# Peripherals.net
KiCad netlist of a schematic drawn in Altium Designer
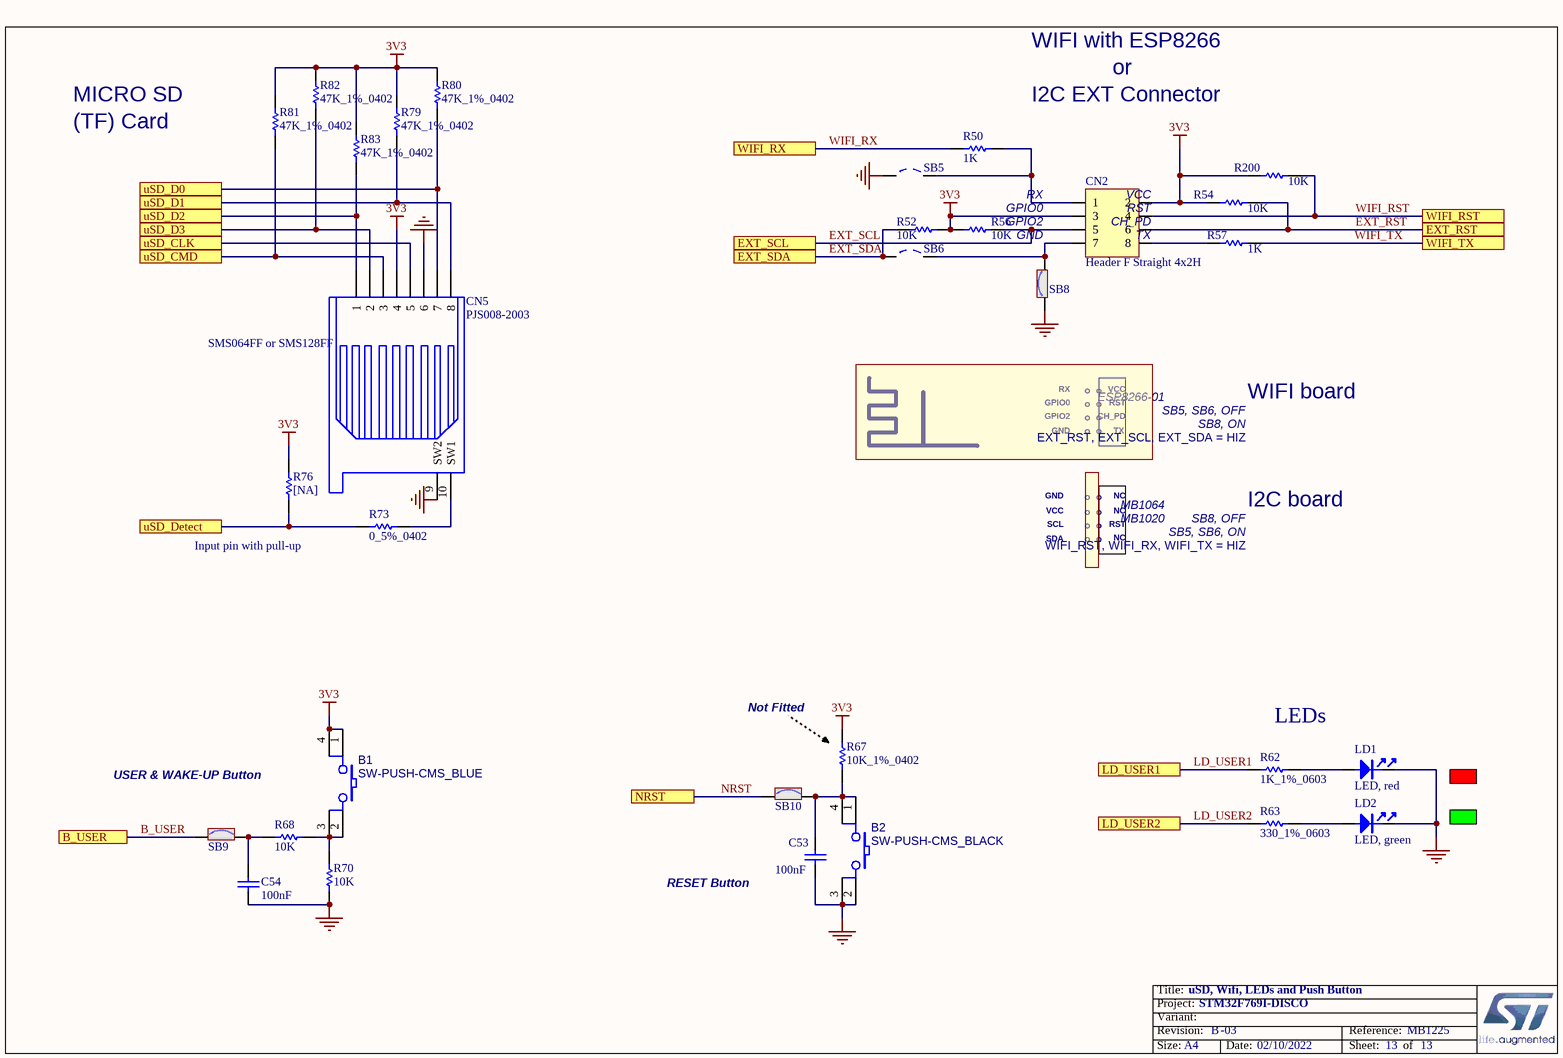
[diagram p0: Peripherals.SchDoc]

(export (version "E")
  (design (tool "Eeschema 10.0.6"))
  (components
    (comp (ref "B1")
      (value "SW-PUSH-CMS_BLUE")
      (footprint "PB10")
      (description "Non-Open Push-Button 0.1A 24V")
      (fields (field (name "PROVIDED") "Sub Co"))
      (libsource (lib "MCD_TOOLS_MISCELLANEOUS") (part "SW-PUSH-CMS_BLUE"))
    )
    (comp (ref "B2")
      (value "SW-PUSH-CMS_BLACK")
      (footprint "PB10")
      (description "Non-Open Push-Button 0.1A 24V")
      (fields (field (name "PROVIDED") "Sub Co"))
      (libsource (lib "MCD_TOOLS_MISCELLANEOUS") (part "SW-PUSH-CMS_BLACK"))
    )
    (comp (ref "C53")
      (value "100nF")
      (footprint "0402C")
      (description "Capacitor,100nF,16V,X7R,10%,0402,YAGEO")
      (libsource (lib "MCD_TOOLS") (part "Cap_100nF_X7R_10%_0402"))
    )
    (comp (ref "C54")
      (value "100nF")
      (footprint "0402C")
      (description "Capacitor,100nF,16V,X7R,10%,0402,YAGEO")
      (libsource (lib "MCD_TOOLS") (part "Cap_100nF_X7R_10%_0402"))
    )
    (comp (ref "CN2")
      (value "Header F Straight 4x2H")
      (footprint "HDR_2X4_2R54")
      (description "Header Female, 4-Pin, Dual row, Straight")
      (libsource (lib "MCD_TOOLS_CONNECTOR") (part "Header 4X2F"))
    )
    (comp (ref "CN5")
      (value "PJS008-2003")
      (footprint "MSD_PJS008_")
      (description "Memory Card Connectors MicroSD Card Conn Revrs Mnt Push-Push")
      (libsource (lib "MCD_TOOLS_CONNECTOR") (part "microSD-PJS008-2003"))
    )
    (comp (ref "LD1")
      (value "LED, red")
      (footprint "0603D")
      (description "LED, red, 0603")
      (libsource (lib "MCD_TOOLS_MISCELLANEOUS") (part "LED_red"))
    )
    (comp (ref "LD2")
      (value "LED, green")
      (footprint "0603D")
      (description "LED, green, 0603")
      (libsource (lib "MCD_TOOLS_MISCELLANEOUS") (part "LED_green"))
    )
    (comp (ref "R50")
      (value "1K")
      (footprint "0402R")
      (description "Resistor,1K,0402,1%,YAGEO")
      (libsource (lib "MCD_TOOLS_RESISTOR") (part "Res_1K_1%_0402"))
    )
    (comp (ref "R52")
      (value "10K")
      (footprint "0402R")
      (description "Resistor,10K,0402,1%,YAGEO")
      (libsource (lib "MCD_TOOLS") (part "Res_10K_1%_0402"))
    )
    (comp (ref "R54")
      (value "10K")
      (footprint "0402R")
      (description "Resistor,10K,0402,1%,YAGEO")
      (libsource (lib "MCD_TOOLS") (part "Res_10K_1%_0402"))
    )
    (comp (ref "R56")
      (value "10K")
      (footprint "0402R")
      (description "Resistor,10K,0402,1%,YAGEO")
      (libsource (lib "MCD_TOOLS") (part "Res_10K_1%_0402"))
    )
    (comp (ref "R57")
      (value "1K")
      (footprint "0402R")
      (description "Resistor,1K,0402,1%,YAGEO")
      (libsource (lib "MCD_TOOLS_RESISTOR") (part "Res_1K_1%_0402"))
    )
    (comp (ref "R62")
      (value "1K_1%_0603")
      (footprint "0603R")
      (description "Resistor,1K,0603,1%,YAGEO")
      (libsource (lib "MCD_TOOLS_RESISTOR") (part "Res_1K_1%_0603"))
    )
    (comp (ref "R63")
      (value "330_1%_0603")
      (footprint "0603R")
      (description "Resistor,330,0603,1%,YAGEO")
      (libsource (lib "MCD_TOOLS_RESISTOR") (part "Res_330_1%_0603"))
    )
    (comp (ref "R67")
      (value "10K_1%_0402")
      (footprint "0402R")
      (description "Resistor,10K,0402,1%,YAGEO")
      (libsource (lib "MCD_TOOLS") (part "Res_10K_1%_0402"))
    )
    (comp (ref "R68")
      (value "10K")
      (footprint "0402R")
      (description "Resistor,10K,0402,1%,YAGEO")
      (libsource (lib "MCD_TOOLS") (part "Res_10K_1%_0402"))
    )
    (comp (ref "R70")
      (value "10K")
      (footprint "0402R")
      (description "Resistor,10K,0402,1%,YAGEO")
      (libsource (lib "MCD_TOOLS") (part "Res_10K_1%_0402"))
    )
    (comp (ref "R73")
      (value "0_5%_0402")
      (footprint "0402R")
      (description "Resistor,0,0402,5%,YAGEO")
      (libsource (lib "MCD_TOOLS") (part "Res_0_5%_0402"))
    )
    (comp (ref "R76")
      (value "[NA]")
      (footprint "0402R")
      (description "Resistor,[NA],0402")
      (libsource (lib "MCD_TOOLS") (part "Res_NA_0402"))
    )
    (comp (ref "R79")
      (value "47K_1%_0402")
      (footprint "0402R")
      (description "Resistor,47K,0402,1%,YAGEO")
      (libsource (lib "MCD_TOOLS") (part "Res_47K_1%_0402"))
    )
    (comp (ref "R80")
      (value "47K_1%_0402")
      (footprint "0402R")
      (description "Resistor,47K,0402,1%,YAGEO")
      (libsource (lib "MCD_TOOLS") (part "Res_47K_1%_0402"))
    )
    (comp (ref "R81")
      (value "47K_1%_0402")
      (footprint "0402R")
      (description "Resistor,47K,0402,1%,YAGEO")
      (libsource (lib "MCD_TOOLS") (part "Res_47K_1%_0402"))
    )
    (comp (ref "R82")
      (value "47K_1%_0402")
      (footprint "0402R")
      (description "Resistor,47K,0402,1%,YAGEO")
      (libsource (lib "MCD_TOOLS") (part "Res_47K_1%_0402"))
    )
    (comp (ref "R83")
      (value "47K_1%_0402")
      (footprint "0402R")
      (description "Resistor,47K,0402,1%,YAGEO")
      (libsource (lib "MCD_TOOLS") (part "Res_47K_1%_0402"))
    )
    (comp (ref "R200")
      (value "10K")
      (footprint "0402R")
      (description "Resistor,10K,0402,1%,YAGEO")
      (libsource (lib "MCD_TOOLS") (part "Res_10K_1%_0402"))
    )
    (comp (ref "SB5")
      (value "Solder Bridge OFF")
      (footprint "JP2_SMD")
      (libsource (lib "MCD_TOOLS") (part "SB_OFF"))
    )
    (comp (ref "SB6")
      (value "Solder Bridge OFF")
      (footprint "JP2_SMD")
      (libsource (lib "MCD_TOOLS") (part "SB_OFF"))
    )
    (comp (ref "SB8") (value "Solder Bridge ON") (footprint "JP2_SMD") (libsource (lib "") (part "SB_ON_1")))
    (comp (ref "SB9")
      (value "Solder Bridge ON")
      (footprint "JP2_SMD")
      (libsource (lib "MCD_TOOLS") (part "SB_ON"))
    )
    (comp (ref "SB10")
      (value "Solder Bridge ON")
      (footprint "JP2_SMD")
      (libsource (lib "MCD_TOOLS") (part "SB_ON"))
    )
  )
  (nets
    (net (code "1") (name "/B_USER") (class "Default")
      (node (ref "SB9") (pin "1") (pinfunction "1_1") (pintype "passive"))
    )
    (net (code "2") (name "/EXT_RST") (class "Default")
      (node (ref "CN2") (pin "6") (pinfunction "6_6") (pintype "passive"))
      (node (ref "R54") (pin "2") (pinfunction "2_2") (pintype "passive"))
    )
    (net (code "3") (name "/EXT_SCL") (class "Default")
      (node (ref "CN2") (pin "5") (pinfunction "5_5") (pintype "passive"))
      (node (ref "R56") (pin "2") (pinfunction "2_2") (pintype "passive"))
    )
    (net (code "4") (name "/EXT_SDA") (class "Default")
      (node (ref "R52") (pin "1") (pinfunction "1_1") (pintype "passive"))
      (node (ref "SB6") (pin "1") (pinfunction "1_1") (pintype "passive"))
    )
    (net (code "5") (name "/LD_USER1") (class "Default")
      (node (ref "R62") (pin "1") (pinfunction "1_1") (pintype "passive"))
    )
    (net (code "6") (name "/LD_USER2") (class "Default")
      (node (ref "R63") (pin "1") (pinfunction "1_1") (pintype "passive"))
    )
    (net (code "7") (name "/NRST") (class "Default")
      (node (ref "SB10") (pin "1") (pinfunction "1_1") (pintype "passive"))
    )
    (net (code "8") (name "/WIFI_RST") (class "Default")
      (node (ref "CN2") (pin "4") (pinfunction "4_4") (pintype "passive"))
      (node (ref "R200") (pin "2") (pinfunction "2_2") (pintype "passive"))
    )
    (net (code "9") (name "/WIFI_RX") (class "Default")
      (node (ref "R50") (pin "1") (pinfunction "1_1") (pintype "passive"))
    )
    (net (code "10") (name "/WIFI_TX") (class "Default")
      (node (ref "R57") (pin "2") (pinfunction "2_2") (pintype "passive"))
    )
    (net (code "11") (name "/uSD_CLK") (class "Default")
      (node (ref "CN5") (pin "5") (pinfunction "5_5") (pintype "passive"))
    )
    (net (code "12") (name "/uSD_CMD") (class "Default")
      (node (ref "CN5") (pin "3") (pinfunction "3_3") (pintype "passive"))
      (node (ref "R81") (pin "1") (pinfunction "1_1") (pintype "passive"))
    )
    (net (code "13") (name "/uSD_D0") (class "Default")
      (node (ref "CN5") (pin "7") (pinfunction "7_7") (pintype "passive"))
      (node (ref "R80") (pin "1") (pinfunction "1_1") (pintype "passive"))
    )
    (net (code "14") (name "/uSD_D1") (class "Default")
      (node (ref "CN5") (pin "8") (pinfunction "8_8") (pintype "passive"))
      (node (ref "R79") (pin "1") (pinfunction "1_1") (pintype "passive"))
    )
    (net (code "15") (name "/uSD_D2") (class "Default")
      (node (ref "CN5") (pin "1") (pinfunction "1_1") (pintype "passive"))
      (node (ref "R83") (pin "1") (pinfunction "1_1") (pintype "passive"))
    )
    (net (code "16") (name "/uSD_D3") (class "Default")
      (node (ref "CN5") (pin "2") (pinfunction "2_2") (pintype "passive"))
      (node (ref "R82") (pin "1") (pinfunction "1_1") (pintype "passive"))
    )
    (net (code "17") (name "/uSD_Detect") (class "Default")
      (node (ref "R73") (pin "1") (pinfunction "1_1") (pintype "passive"))
      (node (ref "R76") (pin "1") (pinfunction "1_1") (pintype "passive"))
    )
    (net (code "18") (name "3V3") (class "Default")
      (node (ref "B1") (pin "1") (pinfunction "1_1") (pintype "passive"))
      (node (ref "B1") (pin "4") (pinfunction "4_4") (pintype "passive"))
      (node (ref "CN2") (pin "2") (pinfunction "2_2") (pintype "passive"))
      (node (ref "CN2") (pin "3") (pinfunction "3_3") (pintype "passive"))
      (node (ref "CN5") (pin "4") (pinfunction "4_4") (pintype "passive"))
      (node (ref "R200") (pin "1") (pinfunction "1_1") (pintype "passive"))
      (node (ref "R52") (pin "2") (pinfunction "2_2") (pintype "passive"))
      (node (ref "R54") (pin "1") (pinfunction "1_1") (pintype "passive"))
      (node (ref "R56") (pin "1") (pinfunction "1_1") (pintype "passive"))
      (node (ref "R67") (pin "2") (pinfunction "2_2") (pintype "passive"))
      (node (ref "R76") (pin "2") (pinfunction "2_2") (pintype "passive"))
      (node (ref "R79") (pin "2") (pinfunction "2_2") (pintype "passive"))
      (node (ref "R80") (pin "2") (pinfunction "2_2") (pintype "passive"))
      (node (ref "R81") (pin "2") (pinfunction "2_2") (pintype "passive"))
      (node (ref "R82") (pin "2") (pinfunction "2_2") (pintype "passive"))
      (node (ref "R83") (pin "2") (pinfunction "2_2") (pintype "passive"))
    )
    (net (code "19") (name "GND") (class "Default")
      (node (ref "B2") (pin "2") (pinfunction "2_2") (pintype "passive"))
      (node (ref "B2") (pin "3") (pinfunction "3_3") (pintype "passive"))
      (node (ref "C53") (pin "1") (pinfunction "1_1") (pintype "passive"))
      (node (ref "C54") (pin "1") (pinfunction "1_1") (pintype "passive"))
      (node (ref "CN5") (pin "6") (pinfunction "6_6") (pintype "passive"))
      (node (ref "CN5") (pin "9") (pinfunction "SW2_9") (pintype "passive"))
      (node (ref "LD1") (pin "2") (pintype "passive"))
      (node (ref "LD2") (pin "2") (pintype "passive"))
      (node (ref "R70") (pin "1") (pinfunction "1_1") (pintype "passive"))
      (node (ref "SB5") (pin "1") (pinfunction "1_1") (pintype "passive"))
      (node (ref "SB8") (pin "1") (pinfunction "1_1") (pintype "passive"))
    )
    (net (code "20") (name "Net-(B1-Pad2)") (class "Default")
      (node (ref "B1") (pin "2") (pinfunction "2_2") (pintype "passive"))
      (node (ref "B1") (pin "3") (pinfunction "3_3") (pintype "passive"))
      (node (ref "R68") (pin "2") (pinfunction "2_2") (pintype "passive"))
      (node (ref "R70") (pin "2") (pinfunction "2_2") (pintype "passive"))
    )
    (net (code "21") (name "Net-(B2-Pad1)") (class "Default")
      (node (ref "B2") (pin "1") (pinfunction "1_1") (pintype "passive"))
      (node (ref "B2") (pin "4") (pinfunction "4_4") (pintype "passive"))
      (node (ref "C53") (pin "2") (pinfunction "2_2") (pintype "passive"))
      (node (ref "R67") (pin "1") (pinfunction "1_1") (pintype "passive"))
      (node (ref "SB10") (pin "2") (pinfunction "2_2") (pintype "passive"))
    )
    (net (code "22") (name "Net-(C54-Pad2)") (class "Default")
      (node (ref "C54") (pin "2") (pinfunction "2_2") (pintype "passive"))
      (node (ref "R68") (pin "1") (pinfunction "1_1") (pintype "passive"))
      (node (ref "SB9") (pin "2") (pinfunction "2_2") (pintype "passive"))
    )
    (net (code "23") (name "Net-(CN2-Pad1)") (class "Default")
      (node (ref "CN2") (pin "1") (pinfunction "1_1") (pintype "passive"))
      (node (ref "R50") (pin "2") (pinfunction "2_2") (pintype "passive"))
      (node (ref "SB5") (pin "2") (pinfunction "2_2") (pintype "passive"))
    )
    (net (code "24") (name "Net-(CN2-Pad7)") (class "Default")
      (node (ref "CN2") (pin "7") (pinfunction "7_7") (pintype "passive"))
      (node (ref "SB6") (pin "2") (pinfunction "2_2") (pintype "passive"))
      (node (ref "SB8") (pin "2") (pinfunction "2_2") (pintype "passive"))
    )
    (net (code "25") (name "Net-(CN2-Pad8)") (class "Default")
      (node (ref "CN2") (pin "8") (pinfunction "8_8") (pintype "passive"))
      (node (ref "R57") (pin "1") (pinfunction "1_1") (pintype "passive"))
    )
    (net (code "26") (name "Net-(CN5-SW1)") (class "Default")
      (node (ref "CN5") (pin "10") (pinfunction "SW1_10") (pintype "passive"))
      (node (ref "R73") (pin "2") (pinfunction "2_2") (pintype "passive"))
    )
    (net (code "27") (name "Net-(LD1-Pad1)") (class "Default")
      (node (ref "LD1") (pin "1") (pintype "passive"))
      (node (ref "R62") (pin "2") (pinfunction "2_2") (pintype "passive"))
    )
    (net (code "28") (name "Net-(LD2-Pad1)") (class "Default")
      (node (ref "LD2") (pin "1") (pintype "passive"))
      (node (ref "R63") (pin "2") (pinfunction "2_2") (pintype "passive"))
    )
  )
)
